# uart2dali_mr3020.net
KiCad netlist of a schematic drawn in EAGLE
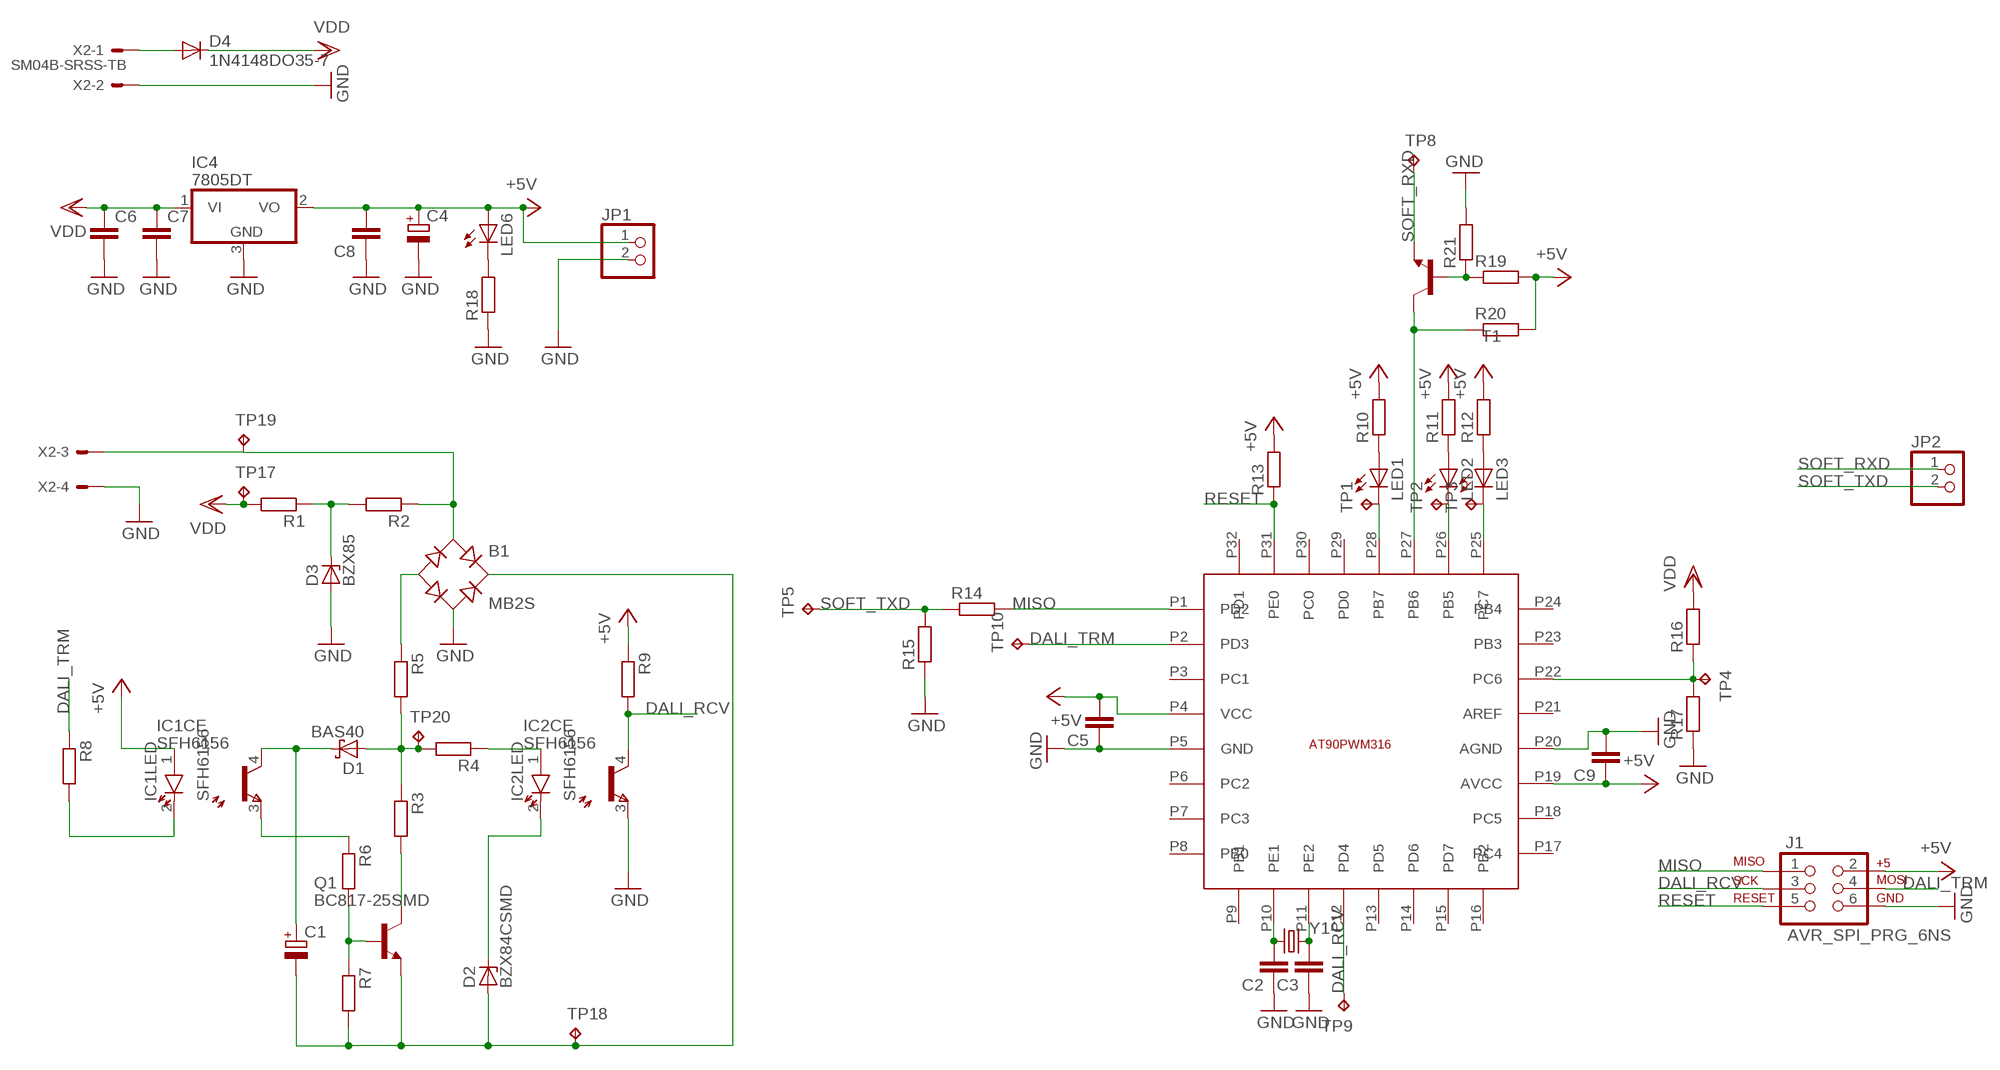
[diagram p0: schematic, sheet 1]

(export (version "E")
  (design (tool "Eeschema 10.0.6"))
  (components
    (comp (ref "B1")
      (value "MB2S")
      (footprint "eagle-import:SOIC-4")
      (libsource (lib "eagle-import") (part "MBS2"))
    )
    (comp (ref "C1")
      (value "CPOL-EUCT6032")
      (footprint "eagle-import:CT6032")
      (libsource (lib "eagle-import") (part "CPOL-EUCT6032"))
    )
    (comp (ref "C2")
      (value "C-EUC0603")
      (footprint "eagle-import:C0603")
      (libsource (lib "eagle-import") (part "C-EUC0603"))
    )
    (comp (ref "C3")
      (value "C-EUC0603")
      (footprint "eagle-import:C0603")
      (libsource (lib "eagle-import") (part "C-EUC0603"))
    )
    (comp (ref "C4")
      (value "CPOL-EUCT7343")
      (footprint "eagle-import:CT7343")
      (libsource (lib "eagle-import") (part "CPOL-EUCT7343"))
    )
    (comp (ref "C5")
      (value "C-EUC0603")
      (footprint "eagle-import:C0603")
      (libsource (lib "eagle-import") (part "C-EUC0603"))
    )
    (comp (ref "C6")
      (value "C-EUC0805")
      (footprint "eagle-import:C0805")
      (libsource (lib "eagle-import") (part "C-EUC0805"))
    )
    (comp (ref "C7")
      (value "C-EUC0805")
      (footprint "eagle-import:C0805")
      (libsource (lib "eagle-import") (part "C-EUC0805"))
    )
    (comp (ref "C8")
      (value "C-EUC0805")
      (footprint "eagle-import:C0805")
      (libsource (lib "eagle-import") (part "C-EUC0805"))
    )
    (comp (ref "C9")
      (value "C-EUC0603")
      (footprint "eagle-import:C0603")
      (libsource (lib "eagle-import") (part "C-EUC0603"))
    )
    (comp (ref "D1")
      (value "BAS40")
      (footprint "eagle-import:SOT23")
      (libsource (lib "eagle-import") (part "BAS40"))
    )
    (comp (ref "D2")
      (value "BZX84CSMD")
      (footprint "eagle-import:TO236")
      (libsource (lib "eagle-import") (part "BZX84CSMD"))
    )
    (comp (ref "D3")
      (value "BZX85")
      (footprint "eagle-import:DO41Z10")
      (libsource (lib "eagle-import") (part "BZX85"))
    )
    (comp (ref "D4")
      (value "1N4148DO35-7")
      (footprint "eagle-import:DO35-7")
      (libsource (lib "eagle-import") (part "1N4148DO35-7"))
    )
    (comp (ref "IC1")
      (value "SFH6156")
      (footprint "eagle-import:SFH")
      (fields (field (name "MF") "VISHAY/TELEFUNKEN") (field (name "MPN") "SFH6156-4T"))
      (libsource (lib "eagle-import") (part "SFH6156"))
    )
    (comp (ref "IC2")
      (value "SFH6156")
      (footprint "eagle-import:SFH")
      (fields (field (name "MF") "VISHAY/TELEFUNKEN") (field (name "MPN") "SFH6156-4T"))
      (libsource (lib "eagle-import") (part "SFH6156"))
    )
    (comp (ref "IC4")
      (value "7805DT")
      (footprint "eagle-import:TO252")
      (libsource (lib "eagle-import") (part "78DT05"))
    )
    (comp (ref "J1")
      (value "AVR_SPI_PRG_6NS")
      (footprint "eagle-import:2X3-NS")
      (libsource (lib "eagle-import") (part "AVR_SPI_PRG_6NS"))
    )
    (comp (ref "JP1")
      (value "PINHD-1X2")
      (footprint "eagle-import:1X02")
      (libsource (lib "eagle-import") (part "PINHD-1X2"))
    )
    (comp (ref "JP2")
      (value "PINHD-1X2")
      (footprint "eagle-import:1X02")
      (libsource (lib "eagle-import") (part "PINHD-1X2"))
    )
    (comp (ref "LED1")
      (value "LEDCHIPLED_0805")
      (footprint "eagle-import:CHIPLED_0805")
      (libsource (lib "eagle-import") (part "LEDCHIPLED_0805"))
    )
    (comp (ref "LED2")
      (value "LEDCHIPLED_0805")
      (footprint "eagle-import:CHIPLED_0805")
      (libsource (lib "eagle-import") (part "LEDCHIPLED_0805"))
    )
    (comp (ref "LED3")
      (value "LEDCHIPLED_0805")
      (footprint "eagle-import:CHIPLED_0805")
      (libsource (lib "eagle-import") (part "LEDCHIPLED_0805"))
    )
    (comp (ref "LED6")
      (value "LEDCHIPLED_0805")
      (footprint "eagle-import:CHIPLED_0805")
      (libsource (lib "eagle-import") (part "LEDCHIPLED_0805"))
    )
    (comp (ref "Q1")
      (value "BC817-25SMD")
      (footprint "eagle-import:SOT23-BEC")
      (libsource (lib "eagle-import") (part "BC817SMD-25"))
    )
    (comp (ref "R1")
      (value "R-EU_0204/7")
      (footprint "eagle-import:0204_7")
      (libsource (lib "eagle-import") (part "R-EU_0204/7"))
    )
    (comp (ref "R2")
      (value "R-EU_0204/7")
      (footprint "eagle-import:0204_7")
      (libsource (lib "eagle-import") (part "R-EU_0204/7"))
    )
    (comp (ref "R3")
      (value "R-EU_R0603")
      (footprint "eagle-import:R0603")
      (libsource (lib "eagle-import") (part "R-EU_R0603"))
    )
    (comp (ref "R4")
      (value "R-EU_R0603")
      (footprint "eagle-import:R0603")
      (libsource (lib "eagle-import") (part "R-EU_R0603"))
    )
    (comp (ref "R5")
      (value "R-EU_R0603")
      (footprint "eagle-import:R0603")
      (libsource (lib "eagle-import") (part "R-EU_R0603"))
    )
    (comp (ref "R6")
      (value "R-EU_R0603")
      (footprint "eagle-import:R0603")
      (libsource (lib "eagle-import") (part "R-EU_R0603"))
    )
    (comp (ref "R7")
      (value "R-EU_R0603")
      (footprint "eagle-import:R0603")
      (libsource (lib "eagle-import") (part "R-EU_R0603"))
    )
    (comp (ref "R8")
      (value "R-EU_R0603")
      (footprint "eagle-import:R0603")
      (libsource (lib "eagle-import") (part "R-EU_R0603"))
    )
    (comp (ref "R9")
      (value "R-EU_R0603")
      (footprint "eagle-import:R0603")
      (libsource (lib "eagle-import") (part "R-EU_R0603"))
    )
    (comp (ref "R10")
      (value "R-EU_R0603")
      (footprint "eagle-import:R0603")
      (libsource (lib "eagle-import") (part "R-EU_R0603"))
    )
    (comp (ref "R11")
      (value "R-EU_R0603")
      (footprint "eagle-import:R0603")
      (libsource (lib "eagle-import") (part "R-EU_R0603"))
    )
    (comp (ref "R12")
      (value "R-EU_R0603")
      (footprint "eagle-import:R0603")
      (libsource (lib "eagle-import") (part "R-EU_R0603"))
    )
    (comp (ref "R13")
      (value "R-EU_R0603")
      (footprint "eagle-import:R0603")
      (libsource (lib "eagle-import") (part "R-EU_R0603"))
    )
    (comp (ref "R14")
      (value "R-EU_R0603")
      (footprint "eagle-import:R0603")
      (libsource (lib "eagle-import") (part "R-EU_R0603"))
    )
    (comp (ref "R15")
      (value "R-EU_R0603")
      (footprint "eagle-import:R0603")
      (libsource (lib "eagle-import") (part "R-EU_R0603"))
    )
    (comp (ref "R16")
      (value "R-EU_R0603")
      (footprint "eagle-import:R0603")
      (libsource (lib "eagle-import") (part "R-EU_R0603"))
    )
    (comp (ref "R17")
      (value "R-EU_R0603")
      (footprint "eagle-import:R0603")
      (libsource (lib "eagle-import") (part "R-EU_R0603"))
    )
    (comp (ref "R18")
      (value "R-EU_R0603")
      (footprint "eagle-import:R0603")
      (libsource (lib "eagle-import") (part "R-EU_R0603"))
    )
    (comp (ref "R19")
      (value "R-EU_R0603")
      (footprint "eagle-import:R0603")
      (libsource (lib "eagle-import") (part "R-EU_R0603"))
    )
    (comp (ref "R20")
      (value "R-EU_R0603")
      (footprint "eagle-import:R0603")
      (libsource (lib "eagle-import") (part "R-EU_R0603"))
    )
    (comp (ref "R21")
      (value "R-EU_R0603")
      (footprint "eagle-import:R0603")
      (libsource (lib "eagle-import") (part "R-EU_R0603"))
    )
    (comp (ref "T1")
      (value "-NPN-SOT23-EBC")
      (footprint "eagle-import:SOT23-EBC")
      (libsource (lib "eagle-import") (part "-NPN-SOT23-EBC"))
    )
    (comp (ref "TP1")
      (value "TPB1,27")
      (footprint "eagle-import:B1,27")
      (libsource (lib "eagle-import") (part "TPB1,27"))
    )
    (comp (ref "TP2")
      (value "TPB1,27")
      (footprint "eagle-import:B1,27")
      (libsource (lib "eagle-import") (part "TPB1,27"))
    )
    (comp (ref "TP3")
      (value "TPB1,27")
      (footprint "eagle-import:B1,27")
      (libsource (lib "eagle-import") (part "TPB1,27"))
    )
    (comp (ref "TP4")
      (value "TPB1,27")
      (footprint "eagle-import:B1,27")
      (libsource (lib "eagle-import") (part "TPB1,27"))
    )
    (comp (ref "TP5")
      (value "TPB1,27")
      (footprint "eagle-import:B1,27")
      (libsource (lib "eagle-import") (part "TPB1,27"))
    )
    (comp (ref "TP8")
      (value "TPB1,27")
      (footprint "eagle-import:B1,27")
      (libsource (lib "eagle-import") (part "TPB1,27"))
    )
    (comp (ref "TP9")
      (value "TPB1,27")
      (footprint "eagle-import:B1,27")
      (libsource (lib "eagle-import") (part "TPB1,27"))
    )
    (comp (ref "TP10")
      (value "TPB1,27")
      (footprint "eagle-import:B1,27")
      (libsource (lib "eagle-import") (part "TPB1,27"))
    )
    (comp (ref "TP17")
      (value "TPB1,27")
      (footprint "eagle-import:B1,27")
      (libsource (lib "eagle-import") (part "TPB1,27"))
    )
    (comp (ref "TP18")
      (value "TPB1,27")
      (footprint "eagle-import:B1,27")
      (libsource (lib "eagle-import") (part "TPB1,27"))
    )
    (comp (ref "TP19")
      (value "TPB1,27")
      (footprint "eagle-import:B1,27")
      (libsource (lib "eagle-import") (part "TPB1,27"))
    )
    (comp (ref "TP20")
      (value "TPB1,27")
      (footprint "eagle-import:B1,27")
      (libsource (lib "eagle-import") (part "TPB1,27"))
    )
    (comp (ref "U$1")
      (value "AT90PWM316")
      (footprint "eagle-import:QFN32_7MM")
      (libsource (lib "eagle-import") (part "AT90PWM316"))
    )
    (comp (ref "X2")
      (value "SM04B-SRSS-TB")
      (footprint "eagle-import:SM04B-SRSS-TB")
      (libsource (lib "eagle-import") (part "?M04B-SRSS-TBS"))
    )
    (comp (ref "Y1")
      (value "CRYSTALTXC-7A")
      (footprint "eagle-import:CRYSTAL-TXC-7A")
      (libsource (lib "eagle-import") (part "CRYSTALTXC-7A"))
    )
  )
  (nets
    (net (code "1") (name "+5V") (class "Default")
      (node (ref "C4") (pin "+") (pinfunction "+_+") (pintype "passive"))
      (node (ref "C5") (pin "2") (pinfunction "2_2") (pintype "passive"))
      (node (ref "C8") (pin "2") (pinfunction "2_2") (pintype "passive"))
      (node (ref "C9") (pin "1") (pinfunction "1_1") (pintype "passive"))
      (node (ref "IC1") (pin "1") (pinfunction "A_1") (pintype "bidirectional"))
      (node (ref "IC4") (pin "2") (pinfunction "VO_2") (pintype "passive"))
      (node (ref "J1") (pin "2") (pinfunction "2_2") (pintype "passive"))
      (node (ref "JP1") (pin "1") (pinfunction "1_1") (pintype "passive"))
      (node (ref "LED6") (pin "A") (pinfunction "A_A") (pintype "passive"))
      (node (ref "R10") (pin "2") (pinfunction "2_2") (pintype "passive"))
      (node (ref "R11") (pin "2") (pinfunction "2_2") (pintype "passive"))
      (node (ref "R12") (pin "2") (pinfunction "2_2") (pintype "passive"))
      (node (ref "R13") (pin "2") (pinfunction "2_2") (pintype "passive"))
      (node (ref "R19") (pin "2") (pinfunction "2_2") (pintype "passive"))
      (node (ref "R20") (pin "2") (pinfunction "2_2") (pintype "passive"))
      (node (ref "R9") (pin "1") (pinfunction "1_1") (pintype "passive"))
      (node (ref "U$1") (pin "P19") (pinfunction "AVCC_P19") (pintype "bidirectional"))
      (node (ref "U$1") (pin "P4") (pinfunction "VCC_P4") (pintype "bidirectional"))
    )
    (net (code "2") (name "/DALI_RCV") (class "Default")
      (node (ref "IC2") (pin "4") (pinfunction "C_4") (pintype "bidirectional"))
      (node (ref "J1") (pin "3") (pinfunction "3_3") (pintype "passive"))
      (node (ref "R9") (pin "2") (pinfunction "2_2") (pintype "passive"))
      (node (ref "TP9") (pin "TP") (pinfunction "TP_TP") (pintype "input"))
      (node (ref "U$1") (pin "P12") (pinfunction "PD4_P12") (pintype "bidirectional"))
    )
    (net (code "3") (name "/DALI_TRM") (class "Default")
      (node (ref "J1") (pin "4") (pinfunction "4_4") (pintype "passive"))
      (node (ref "R8") (pin "1") (pinfunction "1_1") (pintype "passive"))
      (node (ref "TP10") (pin "TP") (pinfunction "TP_TP") (pintype "input"))
      (node (ref "U$1") (pin "P2") (pinfunction "PD3_P2") (pintype "bidirectional"))
    )
    (net (code "4") (name "/MISO") (class "Default")
      (node (ref "J1") (pin "1") (pinfunction "1_1") (pintype "passive"))
      (node (ref "R14") (pin "2") (pinfunction "2_2") (pintype "passive"))
      (node (ref "U$1") (pin "P1") (pinfunction "PD2_P1") (pintype "bidirectional"))
    )
    (net (code "5") (name "/RESET") (class "Default")
      (node (ref "J1") (pin "5") (pinfunction "5_5") (pintype "passive"))
      (node (ref "R13") (pin "1") (pinfunction "1_1") (pintype "passive"))
      (node (ref "U$1") (pin "P31") (pinfunction "PE0_P31") (pintype "bidirectional"))
    )
    (net (code "6") (name "/SOFT_RXD") (class "Default")
      (node (ref "JP2") (pin "1") (pinfunction "1_1") (pintype "passive"))
      (node (ref "T1") (pin "E") (pinfunction "E_E") (pintype "passive"))
      (node (ref "TP8") (pin "TP") (pinfunction "TP_TP") (pintype "input"))
    )
    (net (code "7") (name "/SOFT_TXD") (class "Default")
      (node (ref "JP2") (pin "2") (pinfunction "2_2") (pintype "passive"))
      (node (ref "R14") (pin "1") (pinfunction "1_1") (pintype "passive"))
      (node (ref "R15") (pin "2") (pinfunction "2_2") (pintype "passive"))
      (node (ref "TP5") (pin "TP") (pinfunction "TP_TP") (pintype "input"))
    )
    (net (code "8") (name "GND") (class "Default")
      (node (ref "B1") (pin "~2") (pinfunction "AC2_~2") (pintype "passive"))
      (node (ref "C2") (pin "1") (pinfunction "1_1") (pintype "passive"))
      (node (ref "C3") (pin "1") (pinfunction "1_1") (pintype "passive"))
      (node (ref "C4") (pin "-") (pinfunction "-_-") (pintype "passive"))
      (node (ref "C5") (pin "1") (pinfunction "1_1") (pintype "passive"))
      (node (ref "C6") (pin "2") (pinfunction "2_2") (pintype "passive"))
      (node (ref "C7") (pin "2") (pinfunction "2_2") (pintype "passive"))
      (node (ref "C8") (pin "1") (pinfunction "1_1") (pintype "passive"))
      (node (ref "C9") (pin "2") (pinfunction "2_2") (pintype "passive"))
      (node (ref "D3") (pin "A") (pinfunction "A_A") (pintype "passive"))
      (node (ref "IC2") (pin "3") (pinfunction "E_3") (pintype "bidirectional"))
      (node (ref "IC4") (pin "3") (pinfunction "GND_3") (pintype "passive"))
      (node (ref "J1") (pin "6") (pinfunction "6_6") (pintype "passive"))
      (node (ref "JP1") (pin "2") (pinfunction "2_2") (pintype "passive"))
      (node (ref "R15") (pin "1") (pinfunction "1_1") (pintype "passive"))
      (node (ref "R17") (pin "1") (pinfunction "1_1") (pintype "passive"))
      (node (ref "R18") (pin "1") (pinfunction "1_1") (pintype "passive"))
      (node (ref "R21") (pin "2") (pinfunction "2_2") (pintype "passive"))
      (node (ref "U$1") (pin "P20") (pinfunction "AGND_P20") (pintype "bidirectional"))
      (node (ref "U$1") (pin "P5") (pinfunction "GND_P5") (pintype "bidirectional"))
      (node (ref "X2") (pin "2") (pinfunction "S_2") (pintype "passive"))
      (node (ref "X2") (pin "4") (pinfunction "S_4") (pintype "passive"))
    )
    (net (code "9") (name "Net-(B1-AC1)") (class "Default")
      (node (ref "B1") (pin "~1") (pinfunction "AC1_~1") (pintype "passive"))
      (node (ref "R2") (pin "1") (pinfunction "1_1") (pintype "passive"))
      (node (ref "TP19") (pin "TP") (pinfunction "TP_TP") (pintype "input"))
      (node (ref "X2") (pin "3") (pinfunction "S_3") (pintype "passive"))
    )
    (net (code "10") (name "Net-(B1-Pad+)") (class "Default")
      (node (ref "B1") (pin "+") (pinfunction "+_+") (pintype "passive"))
      (node (ref "C1") (pin "-") (pinfunction "-_-") (pintype "passive"))
      (node (ref "D2") (pin "A") (pinfunction "A_A") (pintype "passive"))
      (node (ref "Q1") (pin "E") (pinfunction "E_E") (pintype "passive"))
      (node (ref "R7") (pin "2") (pinfunction "2_2") (pintype "passive"))
      (node (ref "TP18") (pin "TP") (pinfunction "TP_TP") (pintype "input"))
    )
    (net (code "11") (name "Net-(B1-Pad-)") (class "Default")
      (node (ref "B1") (pin "-") (pinfunction "-_-") (pintype "passive"))
      (node (ref "R5") (pin "1") (pinfunction "1_1") (pintype "passive"))
    )
    (net (code "12") (name "Net-(D1-A)") (class "Default")
      (node (ref "D1") (pin "1") (pinfunction "A_1") (pintype "passive"))
      (node (ref "R3") (pin "1") (pinfunction "1_1") (pintype "passive"))
      (node (ref "R4") (pin "2") (pinfunction "2_2") (pintype "passive"))
      (node (ref "R5") (pin "2") (pinfunction "2_2") (pintype "passive"))
      (node (ref "TP20") (pin "TP") (pinfunction "TP_TP") (pintype "input"))
    )
    (net (code "13") (name "Net-(D1-C)") (class "Default")
      (node (ref "C1") (pin "+") (pinfunction "+_+") (pintype "passive"))
      (node (ref "D1") (pin "3") (pinfunction "C_3") (pintype "passive"))
      (node (ref "IC1") (pin "4") (pinfunction "C_4") (pintype "bidirectional"))
    )
    (net (code "14") (name "Net-(D3-PadC)") (class "Default")
      (node (ref "D3") (pin "C") (pinfunction "C_C") (pintype "passive"))
      (node (ref "R1") (pin "1") (pinfunction "1_1") (pintype "passive"))
      (node (ref "R2") (pin "2") (pinfunction "2_2") (pintype "passive"))
    )
    (net (code "15") (name "Net-(IC1A-E)") (class "Default")
      (node (ref "IC1") (pin "3") (pinfunction "E_3") (pintype "bidirectional"))
      (node (ref "R6") (pin "1") (pinfunction "1_1") (pintype "passive"))
    )
    (net (code "16") (name "Net-(IC1B-K)") (class "Default")
      (node (ref "IC1") (pin "2") (pinfunction "K_2") (pintype "bidirectional"))
      (node (ref "R8") (pin "2") (pinfunction "2_2") (pintype "passive"))
    )
    (net (code "17") (name "Net-(IC2B-A)") (class "Default")
      (node (ref "IC2") (pin "1") (pinfunction "A_1") (pintype "bidirectional"))
      (node (ref "R4") (pin "1") (pinfunction "1_1") (pintype "passive"))
    )
    (net (code "18") (name "Net-(IC2B-K)") (class "Default")
      (node (ref "D2") (pin "C") (pinfunction "C_C") (pintype "passive"))
      (node (ref "IC2") (pin "2") (pinfunction "K_2") (pintype "bidirectional"))
    )
    (net (code "19") (name "Net-(LED1-PadA)") (class "Default")
      (node (ref "LED1") (pin "A") (pinfunction "A_A") (pintype "passive"))
      (node (ref "R10") (pin "1") (pinfunction "1_1") (pintype "passive"))
    )
    (net (code "20") (name "Net-(LED2-PadA)") (class "Default")
      (node (ref "LED2") (pin "A") (pinfunction "A_A") (pintype "passive"))
      (node (ref "R11") (pin "1") (pinfunction "1_1") (pintype "passive"))
    )
    (net (code "21") (name "Net-(LED3-PadA)") (class "Default")
      (node (ref "LED3") (pin "A") (pinfunction "A_A") (pintype "passive"))
      (node (ref "R12") (pin "1") (pinfunction "1_1") (pintype "passive"))
    )
    (net (code "22") (name "Net-(LED6-PadC)") (class "Default")
      (node (ref "LED6") (pin "C") (pinfunction "C_C") (pintype "passive"))
      (node (ref "R18") (pin "2") (pinfunction "2_2") (pintype "passive"))
    )
    (net (code "23") (name "Net-(Q1-PadB)") (class "Default")
      (node (ref "Q1") (pin "B") (pinfunction "B_B") (pintype "passive"))
      (node (ref "R6") (pin "2") (pinfunction "2_2") (pintype "passive"))
      (node (ref "R7") (pin "1") (pinfunction "1_1") (pintype "passive"))
    )
    (net (code "24") (name "Net-(Q1-PadC)") (class "Default")
      (node (ref "Q1") (pin "C") (pinfunction "C_C") (pintype "passive"))
      (node (ref "R3") (pin "2") (pinfunction "2_2") (pintype "passive"))
    )
    (net (code "25") (name "Net-(R19-Pad1)") (class "Default")
      (node (ref "R19") (pin "1") (pinfunction "1_1") (pintype "passive"))
      (node (ref "R21") (pin "1") (pinfunction "1_1") (pintype "passive"))
      (node (ref "T1") (pin "B") (pinfunction "B_B") (pintype "passive"))
    )
    (net (code "26") (name "Net-(U$1-PB5)") (class "Default")
      (node (ref "LED2") (pin "C") (pinfunction "C_C") (pintype "passive"))
      (node (ref "TP2") (pin "TP") (pinfunction "TP_TP") (pintype "input"))
      (node (ref "U$1") (pin "P26") (pinfunction "PB5_P26") (pintype "bidirectional"))
    )
    (net (code "27") (name "Net-(U$1-PB6)") (class "Default")
      (node (ref "R20") (pin "1") (pinfunction "1_1") (pintype "passive"))
      (node (ref "T1") (pin "C") (pinfunction "C_C") (pintype "passive"))
      (node (ref "U$1") (pin "P27") (pinfunction "PB6_P27") (pintype "bidirectional"))
    )
    (net (code "28") (name "Net-(U$1-PB7)") (class "Default")
      (node (ref "LED1") (pin "C") (pinfunction "C_C") (pintype "passive"))
      (node (ref "TP1") (pin "TP") (pinfunction "TP_TP") (pintype "input"))
      (node (ref "U$1") (pin "P28") (pinfunction "PB7_P28") (pintype "bidirectional"))
    )
    (net (code "29") (name "Net-(U$1-PC6)") (class "Default")
      (node (ref "R16") (pin "1") (pinfunction "1_1") (pintype "passive"))
      (node (ref "R17") (pin "2") (pinfunction "2_2") (pintype "passive"))
      (node (ref "TP4") (pin "TP") (pinfunction "TP_TP") (pintype "input"))
      (node (ref "U$1") (pin "P22") (pinfunction "PC6_P22") (pintype "bidirectional"))
    )
    (net (code "30") (name "Net-(U$1-PC7)") (class "Default")
      (node (ref "LED3") (pin "C") (pinfunction "C_C") (pintype "passive"))
      (node (ref "TP3") (pin "TP") (pinfunction "TP_TP") (pintype "input"))
      (node (ref "U$1") (pin "P25") (pinfunction "PC7_P25") (pintype "bidirectional"))
    )
    (net (code "31") (name "Net-(U$1-PE1)") (class "Default")
      (node (ref "C2") (pin "2") (pinfunction "2_2") (pintype "passive"))
      (node (ref "U$1") (pin "P10") (pinfunction "PE1_P10") (pintype "bidirectional"))
      (node (ref "Y1") (pin "P$1") (pinfunction "1_P$1") (pintype "passive"))
    )
    (net (code "32") (name "Net-(U$1-PE2)") (class "Default")
      (node (ref "C3") (pin "2") (pinfunction "2_2") (pintype "passive"))
      (node (ref "U$1") (pin "P11") (pinfunction "PE2_P11") (pintype "bidirectional"))
      (node (ref "Y1") (pin "P$2") (pinfunction "2_P$2") (pintype "passive"))
    )
    (net (code "33") (name "Net-(X2A-S)") (class "Default")
      (node (ref "D4") (pin "A") (pinfunction "A_A") (pintype "passive"))
      (node (ref "X2") (pin "1") (pinfunction "S_1") (pintype "passive"))
    )
    (net (code "34") (name "VDD") (class "Default")
      (node (ref "C6") (pin "1") (pinfunction "1_1") (pintype "passive"))
      (node (ref "C7") (pin "1") (pinfunction "1_1") (pintype "passive"))
      (node (ref "D4") (pin "C") (pinfunction "C_C") (pintype "passive"))
      (node (ref "IC4") (pin "1") (pinfunction "VI_1") (pintype "input"))
      (node (ref "R1") (pin "2") (pinfunction "2_2") (pintype "passive"))
      (node (ref "R16") (pin "2") (pinfunction "2_2") (pintype "passive"))
      (node (ref "TP17") (pin "TP") (pinfunction "TP_TP") (pintype "input"))
    )
    (net (code "35") (name "unconnected-(U$1-AREF-PadP21)") (class "Default")
      (node (ref "U$1") (pin "P21") (pinfunction "AREF_P21") (pintype "bidirectional"))
    )
    (net (code "36") (name "unconnected-(U$1-PB0-PadP8)") (class "Default")
      (node (ref "U$1") (pin "P8") (pinfunction "PB0_P8") (pintype "bidirectional"))
    )
    (net (code "37") (name "unconnected-(U$1-PB1-PadP9)") (class "Default")
      (node (ref "U$1") (pin "P9") (pinfunction "PB1_P9") (pintype "bidirectional"))
    )
    (net (code "38") (name "unconnected-(U$1-PB2-PadP16)") (class "Default")
      (node (ref "U$1") (pin "P16") (pinfunction "PB2_P16") (pintype "bidirectional"))
    )
    (net (code "39") (name "unconnected-(U$1-PB3-PadP23)") (class "Default")
      (node (ref "U$1") (pin "P23") (pinfunction "PB3_P23") (pintype "bidirectional"))
    )
    (net (code "40") (name "unconnected-(U$1-PB4-PadP24)") (class "Default")
      (node (ref "U$1") (pin "P24") (pinfunction "PB4_P24") (pintype "bidirectional"))
    )
    (net (code "41") (name "unconnected-(U$1-PC0-PadP30)") (class "Default")
      (node (ref "U$1") (pin "P30") (pinfunction "PC0_P30") (pintype "bidirectional"))
    )
    (net (code "42") (name "unconnected-(U$1-PC1-PadP3)") (class "Default")
      (node (ref "U$1") (pin "P3") (pinfunction "PC1_P3") (pintype "bidirectional"))
    )
    (net (code "43") (name "unconnected-(U$1-PC2-PadP6)") (class "Default")
      (node (ref "U$1") (pin "P6") (pinfunction "PC2_P6") (pintype "bidirectional"))
    )
    (net (code "44") (name "unconnected-(U$1-PC3-PadP7)") (class "Default")
      (node (ref "U$1") (pin "P7") (pinfunction "PC3_P7") (pintype "bidirectional"))
    )
    (net (code "45") (name "unconnected-(U$1-PC4-PadP17)") (class "Default")
      (node (ref "U$1") (pin "P17") (pinfunction "PC4_P17") (pintype "bidirectional"))
    )
    (net (code "46") (name "unconnected-(U$1-PC5-PadP18)") (class "Default")
      (node (ref "U$1") (pin "P18") (pinfunction "PC5_P18") (pintype "bidirectional"))
    )
    (net (code "47") (name "unconnected-(U$1-PD0-PadP29)") (class "Default")
      (node (ref "U$1") (pin "P29") (pinfunction "PD0_P29") (pintype "bidirectional"))
    )
    (net (code "48") (name "unconnected-(U$1-PD1-PadP32)") (class "Default")
      (node (ref "U$1") (pin "P32") (pinfunction "PD1_P32") (pintype "bidirectional"))
    )
    (net (code "49") (name "unconnected-(U$1-PD5-PadP13)") (class "Default")
      (node (ref "U$1") (pin "P13") (pinfunction "PD5_P13") (pintype "bidirectional"))
    )
    (net (code "50") (name "unconnected-(U$1-PD6-PadP14)") (class "Default")
      (node (ref "U$1") (pin "P14") (pinfunction "PD6_P14") (pintype "bidirectional"))
    )
    (net (code "51") (name "unconnected-(U$1-PD7-PadP15)") (class "Default")
      (node (ref "U$1") (pin "P15") (pinfunction "PD7_P15") (pintype "bidirectional"))
    )
  )
)
